# dtack-generator.net
KiCad netlist of a schematic drawn in EAGLE
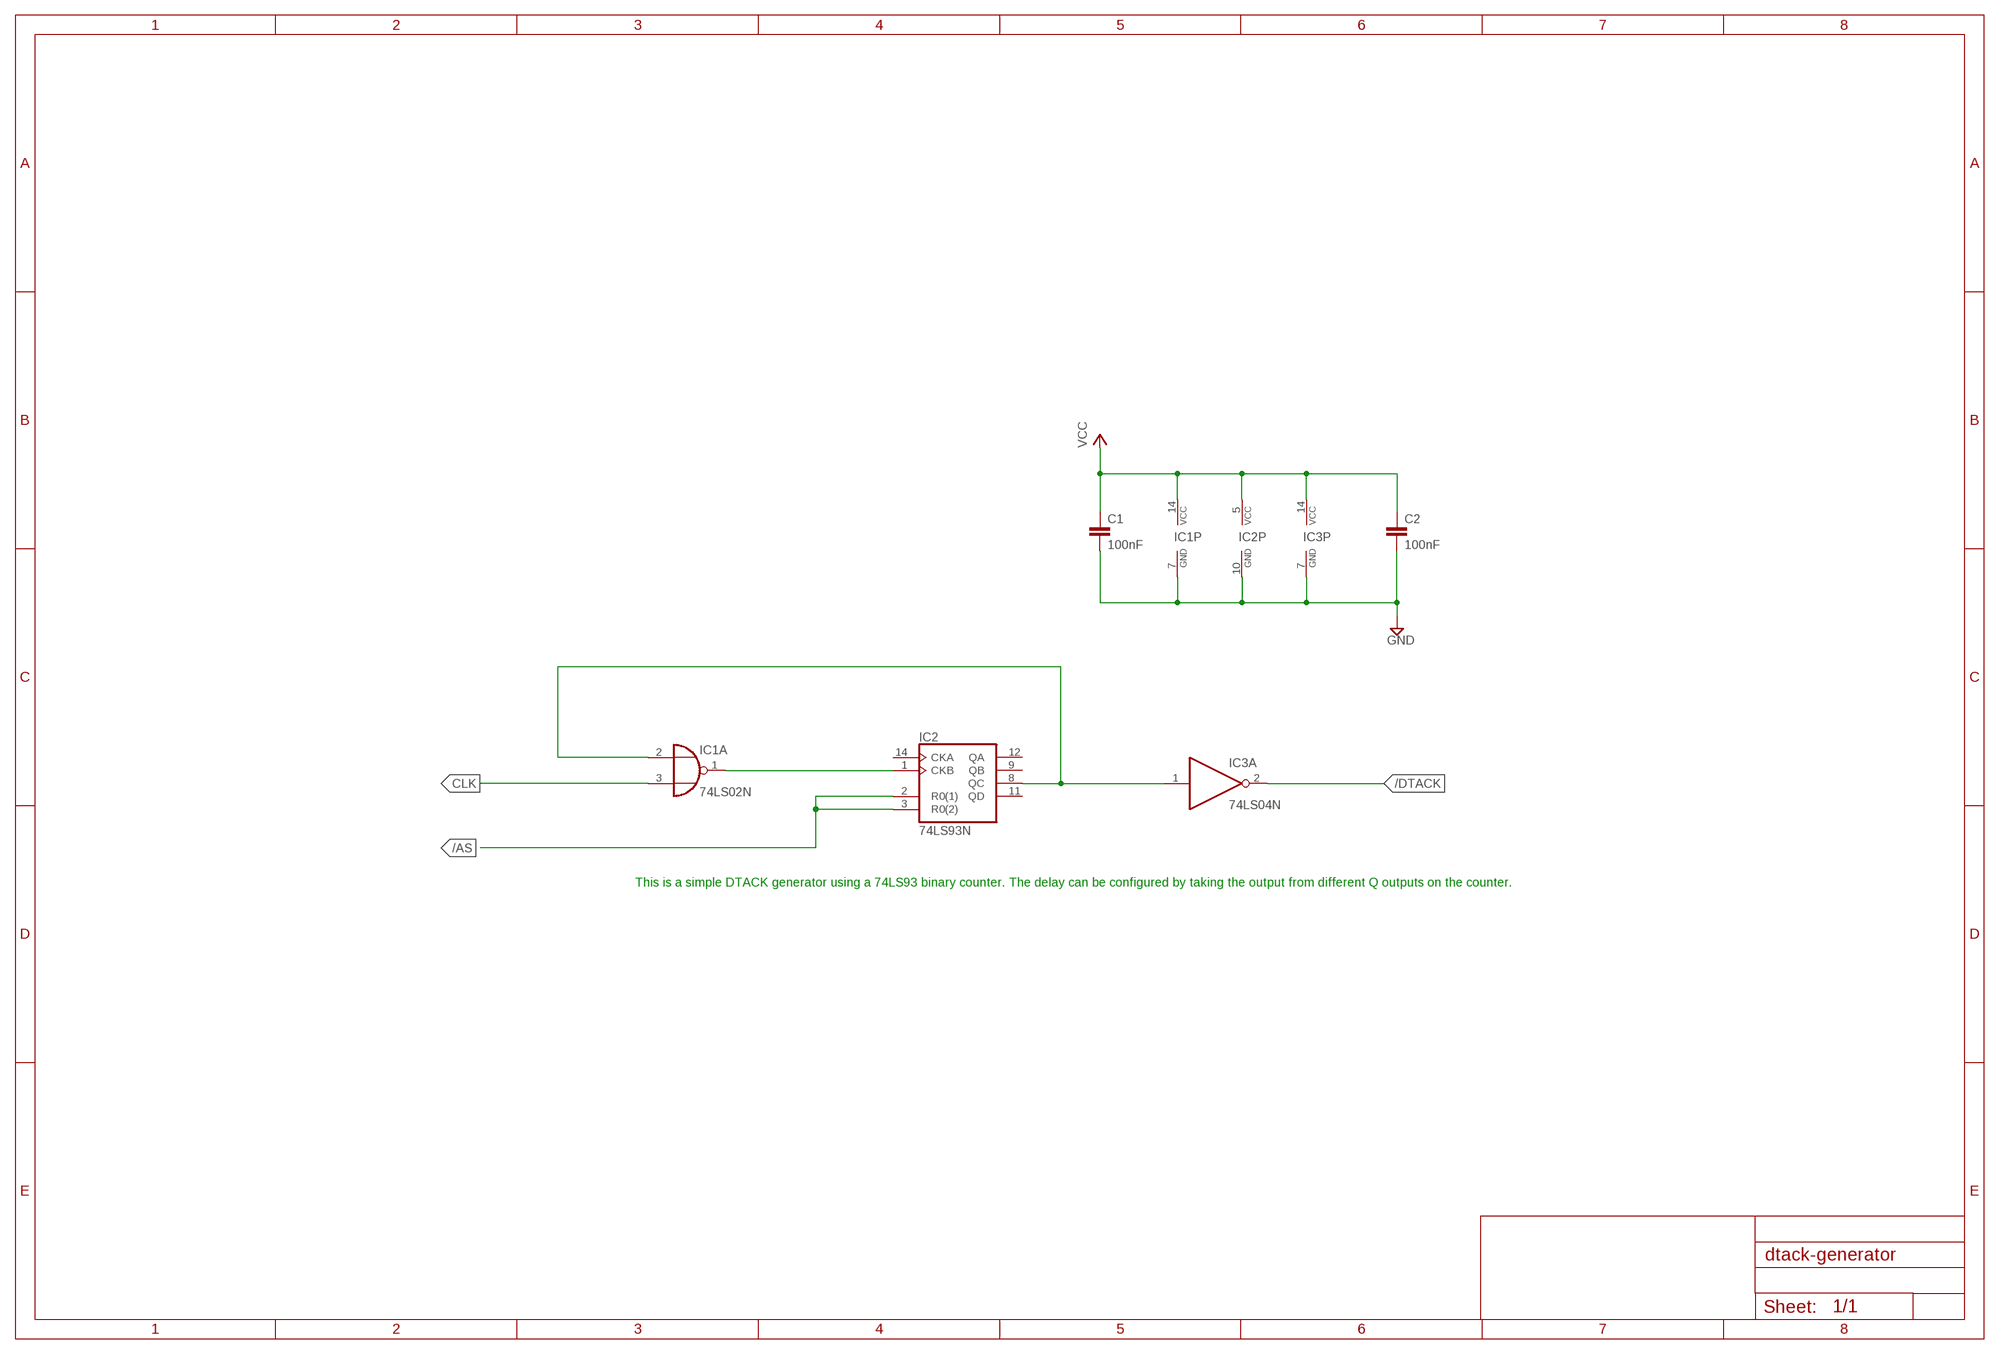
[diagram p0: schematic, sheet 1]

(export (version "E")
  (design (tool "Eeschema 10.0.6"))
  (components
    (comp (ref "C1")
      (value "100nF")
      (footprint "eagle-import:C025-024X044")
      (libsource (lib "eagle-import") (part "C-EU025-024X044"))
    )
    (comp (ref "C2")
      (value "100nF")
      (footprint "eagle-import:C025-024X044")
      (libsource (lib "eagle-import") (part "C-EU025-024X044"))
    )
    (comp (ref "IC1")
      (value "74LS02N")
      (footprint "eagle-import:DIL14")
      (libsource (lib "eagle-import") (part "7402NLS"))
    )
    (comp (ref "IC2")
      (value "74LS93N")
      (footprint "eagle-import:DIL14")
      (libsource (lib "eagle-import") (part "7493NLS"))
    )
    (comp (ref "IC3")
      (value "74LS04N")
      (footprint "eagle-import:DIL14")
      (libsource (lib "eagle-import") (part "7404NLS"))
    )
  )
  (nets
    (net (code "1") (name "CLK") (class "Default")
      (node (ref "IC1") (pin "3") (pinfunction "I1_3") (pintype "input"))
    )
    (net (code "2") (name "GND") (class "Default")
      (node (ref "C1") (pin "2") (pinfunction "2_2") (pintype "passive"))
      (node (ref "C2") (pin "2") (pinfunction "2_2") (pintype "passive"))
      (node (ref "IC1") (pin "7") (pinfunction "GND_7") (pintype "power_in"))
      (node (ref "IC2") (pin "10") (pinfunction "GND_10") (pintype "power_in"))
      (node (ref "IC3") (pin "7") (pinfunction "GND_7") (pintype "power_in"))
    )
    (net (code "3") (name "Net-(IC1A-I0)") (class "Default")
      (node (ref "IC1") (pin "2") (pinfunction "I0_2") (pintype "input"))
      (node (ref "IC2") (pin "8") (pinfunction "QC_8") (pintype "output"))
      (node (ref "IC3") (pin "1") (pinfunction "I_1") (pintype "input"))
    )
    (net (code "4") (name "Net-(IC1A-O)") (class "Default")
      (node (ref "IC1") (pin "1") (pinfunction "O_1") (pintype "output"))
      (node (ref "IC2") (pin "1") (pinfunction "CKB_1") (pintype "input"))
    )
    (net (code "5") (name "VCC") (class "Default")
      (node (ref "C1") (pin "1") (pinfunction "1_1") (pintype "passive"))
      (node (ref "C2") (pin "1") (pinfunction "1_1") (pintype "passive"))
      (node (ref "IC1") (pin "14") (pinfunction "VCC_14") (pintype "power_in"))
      (node (ref "IC2") (pin "5") (pinfunction "VCC_5") (pintype "power_in"))
      (node (ref "IC3") (pin "14") (pinfunction "VCC_14") (pintype "power_in"))
    )
    (net (code "6") (name "unconnected-(IC2A-CKA-Pad14)") (class "Default")
      (node (ref "IC2") (pin "14") (pinfunction "CKA_14") (pintype "input"))
    )
    (net (code "7") (name "unconnected-(IC2A-QA-Pad12)") (class "Default")
      (node (ref "IC2") (pin "12") (pinfunction "QA_12") (pintype "output"))
    )
    (net (code "8") (name "unconnected-(IC2A-QB-Pad9)") (class "Default")
      (node (ref "IC2") (pin "9") (pinfunction "QB_9") (pintype "output"))
    )
    (net (code "9") (name "unconnected-(IC2A-QD-Pad11)") (class "Default")
      (node (ref "IC2") (pin "11") (pinfunction "QD_11") (pintype "output"))
    )
    (net (code "10") (name "{slash}AS") (class "Default")
      (node (ref "IC2") (pin "2") (pinfunction "R0(1)_2") (pintype "input"))
      (node (ref "IC2") (pin "3") (pinfunction "R0(2)_3") (pintype "input"))
    )
    (net (code "11") (name "{slash}DTACK") (class "Default")
      (node (ref "IC3") (pin "2") (pinfunction "O_2") (pintype "output"))
    )
  )
)
